# GPIO_HEADER.net
KiCad netlist of a schematic drawn in Altium Designer
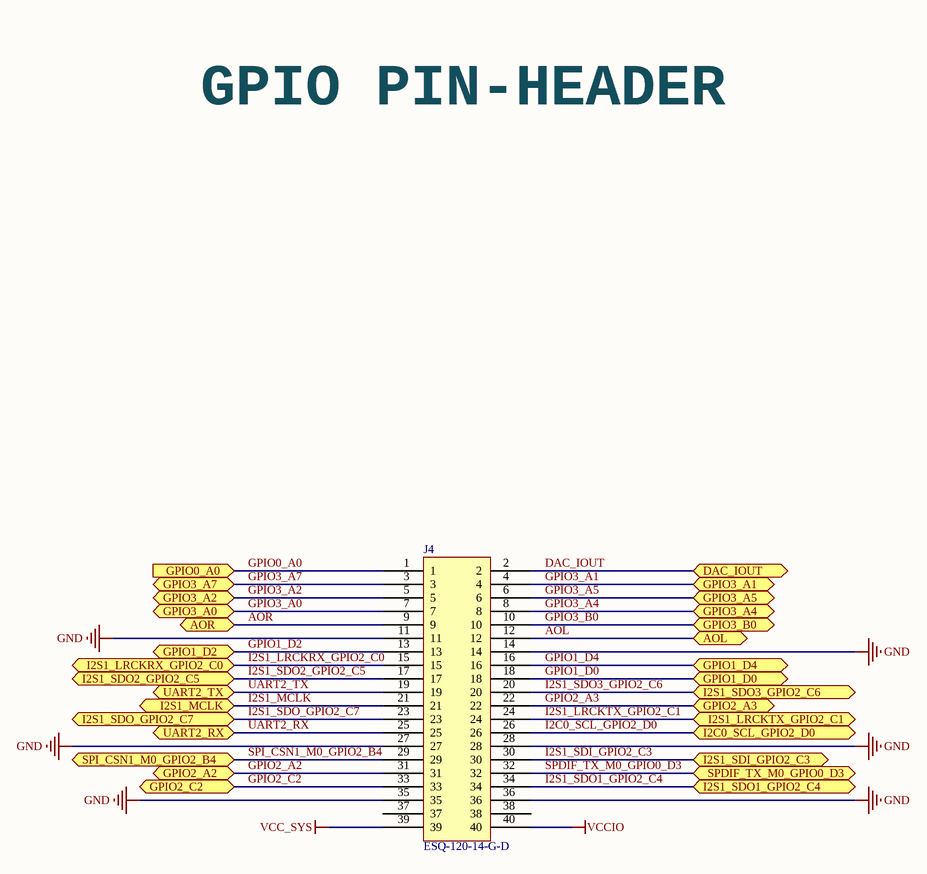
[diagram p0: GPIO_HEADER.SchDoc]

(export (version "E")
  (design (tool "Eeschema 10.0.6"))
  (components
    (comp (ref "J4")
      (value "ESQ-120-14-G-D")
      (footprint "ESQ-120-14-G-D")
      (description "CONN RCPT 40POS .100\" DUAL GOLD")
      (fields
        (field (name "MFR") "Samtec Inc.")
        (field (name ".CREATOR") "MM")
        (field (name ".CHECKED PCB") "MM")
        (field (name ".CHECKED SCH") "MM")
      )
      (libsource (lib "AAR_RockChip_RK3328") (part "ESQ-120-14-G-D"))
    )
  )
  (nets
    (net (code "1") (name "/AOL") (class "Default")
      (node (ref "J4") (pin "12") (pinfunction "12_12") (pintype "passive"))
    )
    (net (code "2") (name "/AOR") (class "Default")
      (node (ref "J4") (pin "9") (pinfunction "9_9") (pintype "passive"))
    )
    (net (code "3") (name "/DAC_IOUT") (class "Default")
      (node (ref "J4") (pin "2") (pinfunction "2_2") (pintype "passive"))
    )
    (net (code "4") (name "/GPIO0_A0") (class "Default")
      (node (ref "J4") (pin "1") (pinfunction "1_1") (pintype "passive"))
    )
    (net (code "5") (name "/GPIO1_D0") (class "Default")
      (node (ref "J4") (pin "18") (pinfunction "18_18") (pintype "passive"))
    )
    (net (code "6") (name "/GPIO1_D2") (class "Default")
      (node (ref "J4") (pin "13") (pinfunction "13_13") (pintype "passive"))
    )
    (net (code "7") (name "/GPIO1_D4") (class "Default")
      (node (ref "J4") (pin "16") (pinfunction "16_16") (pintype "passive"))
    )
    (net (code "8") (name "/GPIO2_A2") (class "Default")
      (node (ref "J4") (pin "31") (pinfunction "31_31") (pintype "passive"))
    )
    (net (code "9") (name "/GPIO2_A3") (class "Default")
      (node (ref "J4") (pin "22") (pinfunction "22_22") (pintype "passive"))
    )
    (net (code "10") (name "/GPIO2_C2") (class "Default")
      (node (ref "J4") (pin "33") (pinfunction "33_33") (pintype "passive"))
    )
    (net (code "11") (name "/GPIO3_A0") (class "Default")
      (node (ref "J4") (pin "7") (pinfunction "7_7") (pintype "passive"))
    )
    (net (code "12") (name "/GPIO3_A1") (class "Default")
      (node (ref "J4") (pin "4") (pinfunction "4_4") (pintype "passive"))
    )
    (net (code "13") (name "/GPIO3_A2") (class "Default")
      (node (ref "J4") (pin "5") (pinfunction "5_5") (pintype "passive"))
    )
    (net (code "14") (name "/GPIO3_A4") (class "Default")
      (node (ref "J4") (pin "8") (pinfunction "8_8") (pintype "passive"))
    )
    (net (code "15") (name "/GPIO3_A5") (class "Default")
      (node (ref "J4") (pin "6") (pinfunction "6_6") (pintype "passive"))
    )
    (net (code "16") (name "/GPIO3_A7") (class "Default")
      (node (ref "J4") (pin "3") (pinfunction "3_3") (pintype "passive"))
    )
    (net (code "17") (name "/GPIO3_B0") (class "Default")
      (node (ref "J4") (pin "10") (pinfunction "10_10") (pintype "passive"))
    )
    (net (code "18") (name "/I2C0_SCL_GPIO2_D0") (class "Default")
      (node (ref "J4") (pin "26") (pinfunction "26_26") (pintype "passive"))
    )
    (net (code "19") (name "/I2S1_LRCKRX_GPIO2_C0") (class "Default")
      (node (ref "J4") (pin "15") (pinfunction "15_15") (pintype "passive"))
    )
    (net (code "20") (name "/I2S1_LRCKTX_GPIO2_C1") (class "Default")
      (node (ref "J4") (pin "24") (pinfunction "24_24") (pintype "passive"))
    )
    (net (code "21") (name "/I2S1_MCLK") (class "Default")
      (node (ref "J4") (pin "21") (pinfunction "21_21") (pintype "passive"))
    )
    (net (code "22") (name "/I2S1_SDI_GPIO2_C3") (class "Default")
      (node (ref "J4") (pin "30") (pinfunction "30_30") (pintype "passive"))
    )
    (net (code "23") (name "/I2S1_SDO1_GPIO2_C4") (class "Default")
      (node (ref "J4") (pin "34") (pinfunction "34_34") (pintype "passive"))
    )
    (net (code "24") (name "/I2S1_SDO2_GPIO2_C5") (class "Default")
      (node (ref "J4") (pin "17") (pinfunction "17_17") (pintype "passive"))
    )
    (net (code "25") (name "/I2S1_SDO3_GPIO2_C6") (class "Default")
      (node (ref "J4") (pin "20") (pinfunction "20_20") (pintype "passive"))
    )
    (net (code "26") (name "/I2S1_SDO_GPIO2_C7") (class "Default")
      (node (ref "J4") (pin "23") (pinfunction "23_23") (pintype "passive"))
    )
    (net (code "27") (name "/SPDIF_TX_M0_GPIO0_D3") (class "Default")
      (node (ref "J4") (pin "32") (pinfunction "32_32") (pintype "passive"))
    )
    (net (code "28") (name "/SPI_CSN1_M0_GPIO2_B4") (class "Default")
      (node (ref "J4") (pin "29") (pinfunction "29_29") (pintype "passive"))
    )
    (net (code "29") (name "/UART2_RX") (class "Default")
      (node (ref "J4") (pin "25") (pinfunction "25_25") (pintype "passive"))
    )
    (net (code "30") (name "/UART2_TX") (class "Default")
      (node (ref "J4") (pin "19") (pinfunction "19_19") (pintype "passive"))
    )
    (net (code "31") (name "GND") (class "Default")
      (node (ref "J4") (pin "11") (pinfunction "11_11") (pintype "passive"))
      (node (ref "J4") (pin "14") (pinfunction "14_14") (pintype "passive"))
      (node (ref "J4") (pin "27") (pinfunction "27_27") (pintype "passive"))
      (node (ref "J4") (pin "28") (pinfunction "28_28") (pintype "passive"))
      (node (ref "J4") (pin "35") (pinfunction "35_35") (pintype "passive"))
      (node (ref "J4") (pin "36") (pinfunction "36_36") (pintype "passive"))
    )
    (net (code "32") (name "VCCIO") (class "Default")
      (node (ref "J4") (pin "40") (pinfunction "40_40") (pintype "passive"))
    )
    (net (code "33") (name "VCC_SYS") (class "Default")
      (node (ref "J4") (pin "39") (pinfunction "39_39") (pintype "passive"))
    )
    (net (code "34") (name "unconnected-(J4-Pad37)") (class "Default")
      (node (ref "J4") (pin "37") (pinfunction "37_37") (pintype "passive"))
    )
    (net (code "35") (name "unconnected-(J4-Pad38)") (class "Default")
      (node (ref "J4") (pin "38") (pinfunction "38_38") (pintype "passive"))
    )
  )
)
